# SCH_5_Vibration_Motor.net
KiCad netlist of a schematic drawn in Altium Designer
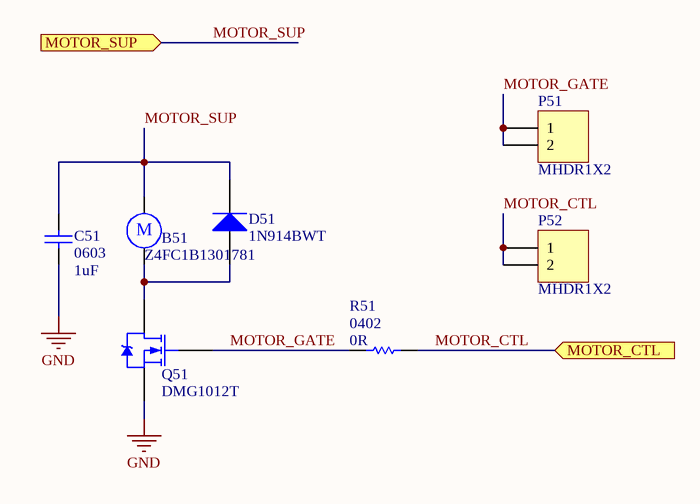
[diagram p0: SCH_5_Vibration Motor.SchDoc]

(export (version "E")
  (design (tool "Eeschema 10.0.6"))
  (components
    (comp (ref "B51")
      (value "Z4FC1B1301781")
      (footprint "Z4FC1B1301781")
      (description "VIBRATION MOTOR CYL 2.7V SMD")
      (fields (field (name "MANUFACTURER") "Jinlong Machinery & Electronics"))
      (libsource (lib "Schematic_Motors") (part "Z4FC1B1301781"))
    )
    (comp (ref "C51")
      (value "0603")
      (footprint "CAPC1608X10N")
      (description "Capacitor")
      (fields (field (name "ALTIUM_VALUE") "1uF") (field (name "PUBLISHER") "Altium Limited"))
      (libsource (lib "Miscellaneous Devices") (part "Cap"))
    )
    (comp (ref "D51")
      (value "1N914BWT")
      (footprint "SODFL160X70-2N")
      (description "DIODE GEN PURP 75V 200MA SOD523F")
      (fields (field (name "MANUFACTURER") "ON Semiconductor / Fairchild"))
      (libsource (lib "Schematic_Diode") (part "1N914BWT"))
    )
    (comp (ref "P51")
      (value "MHDR1X2")
      (footprint "MHDR1X2")
      (description "Header, 2-Pin")
      (fields (field (name "PUBLISHER") "Altium Limited"))
      (libsource (lib "Miscellaneous Connectors") (part "MHDR1X2"))
    )
    (comp (ref "P52")
      (value "MHDR1X2")
      (footprint "MHDR1X2")
      (description "Header, 2-Pin")
      (fields (field (name "PUBLISHER") "Altium Limited"))
      (libsource (lib "Miscellaneous Connectors") (part "MHDR1X2"))
    )
    (comp (ref "Q51")
      (value "DMG1012T")
      (footprint "SOT65P200X125X95-3N")
      (description "MOSFET N-CH 20V 630MA SOT-523")
      (fields (field (name "MANUFACTURER") "Diodes") (field (name "MANUFACTURER PART NUMBER") "DMG1012T-7"))
      (libsource (lib "Schematic_Transistors") (part "DMG1012T-7"))
    )
    (comp (ref "R51")
      (value "0402")
      (footprint "RESC1005X04N")
      (description "Resistor")
      (fields (field (name "ALTIUM_VALUE") "0R") (field (name "PUBLISHER") "Altium Limited"))
      (libsource (lib "Miscellaneous Devices") (part "Res1"))
    )
  )
  (nets
    (net (code "1") (name "/MOTOR_CTL") (class "Default")
      (node (ref "P52") (pin "1") (pinfunction "1_1") (pintype "passive"))
      (node (ref "P52") (pin "2") (pinfunction "2_2") (pintype "passive"))
      (node (ref "R51") (pin "2") (pinfunction "2_2") (pintype "passive"))
    )
    (net (code "2") (name "/MOTOR_GATE") (class "Default")
      (node (ref "P51") (pin "1") (pinfunction "1_1") (pintype "passive"))
      (node (ref "P51") (pin "2") (pinfunction "2_2") (pintype "passive"))
      (node (ref "Q51") (pin "1") (pinfunction "G_1") (pintype "passive"))
      (node (ref "R51") (pin "1") (pinfunction "1_1") (pintype "passive"))
    )
    (net (code "3") (name "/MOTOR_SUP") (class "Default")
      (node (ref "B51") (pin "1") (pinfunction "1_1") (pintype "passive"))
      (node (ref "C51") (pin "2") (pinfunction "2_2") (pintype "passive"))
      (node (ref "D51") (pin "2") (pinfunction "K_2") (pintype "passive"))
    )
    (net (code "4") (name "GND") (class "Default")
      (node (ref "C51") (pin "1") (pinfunction "1_1") (pintype "passive"))
      (node (ref "Q51") (pin "2") (pinfunction "S_2") (pintype "passive"))
    )
    (net (code "5") (name "Net-(D51-A)") (class "Default")
      (node (ref "B51") (pin "2") (pinfunction "2_2") (pintype "passive"))
      (node (ref "D51") (pin "1") (pinfunction "A_1") (pintype "passive"))
      (node (ref "Q51") (pin "3") (pinfunction "D_3") (pintype "passive"))
    )
  )
)
